# Tingle_v3.net
KiCad netlist of a schematic drawn in EAGLE
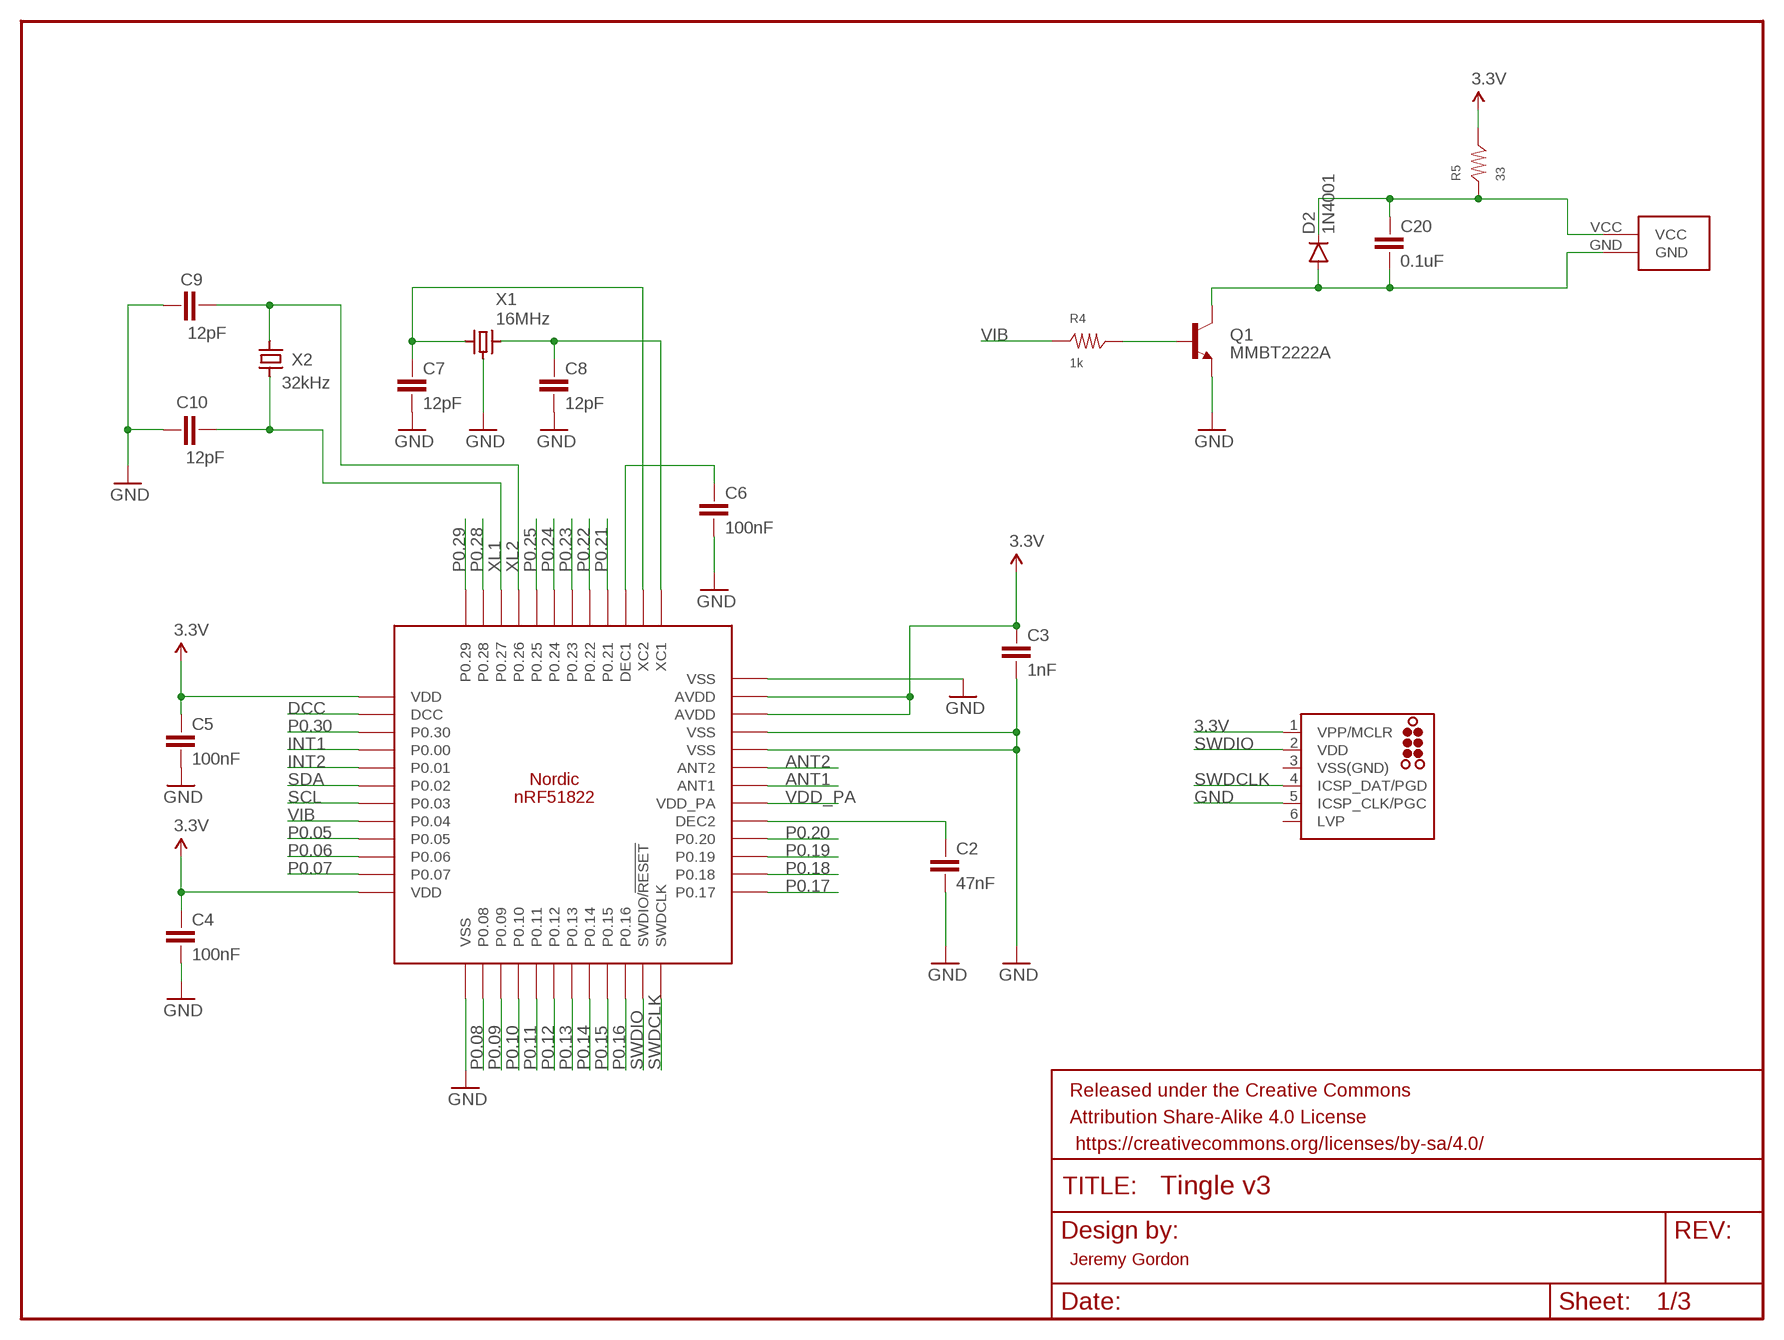
[diagram p0: schematic, sheet 1]
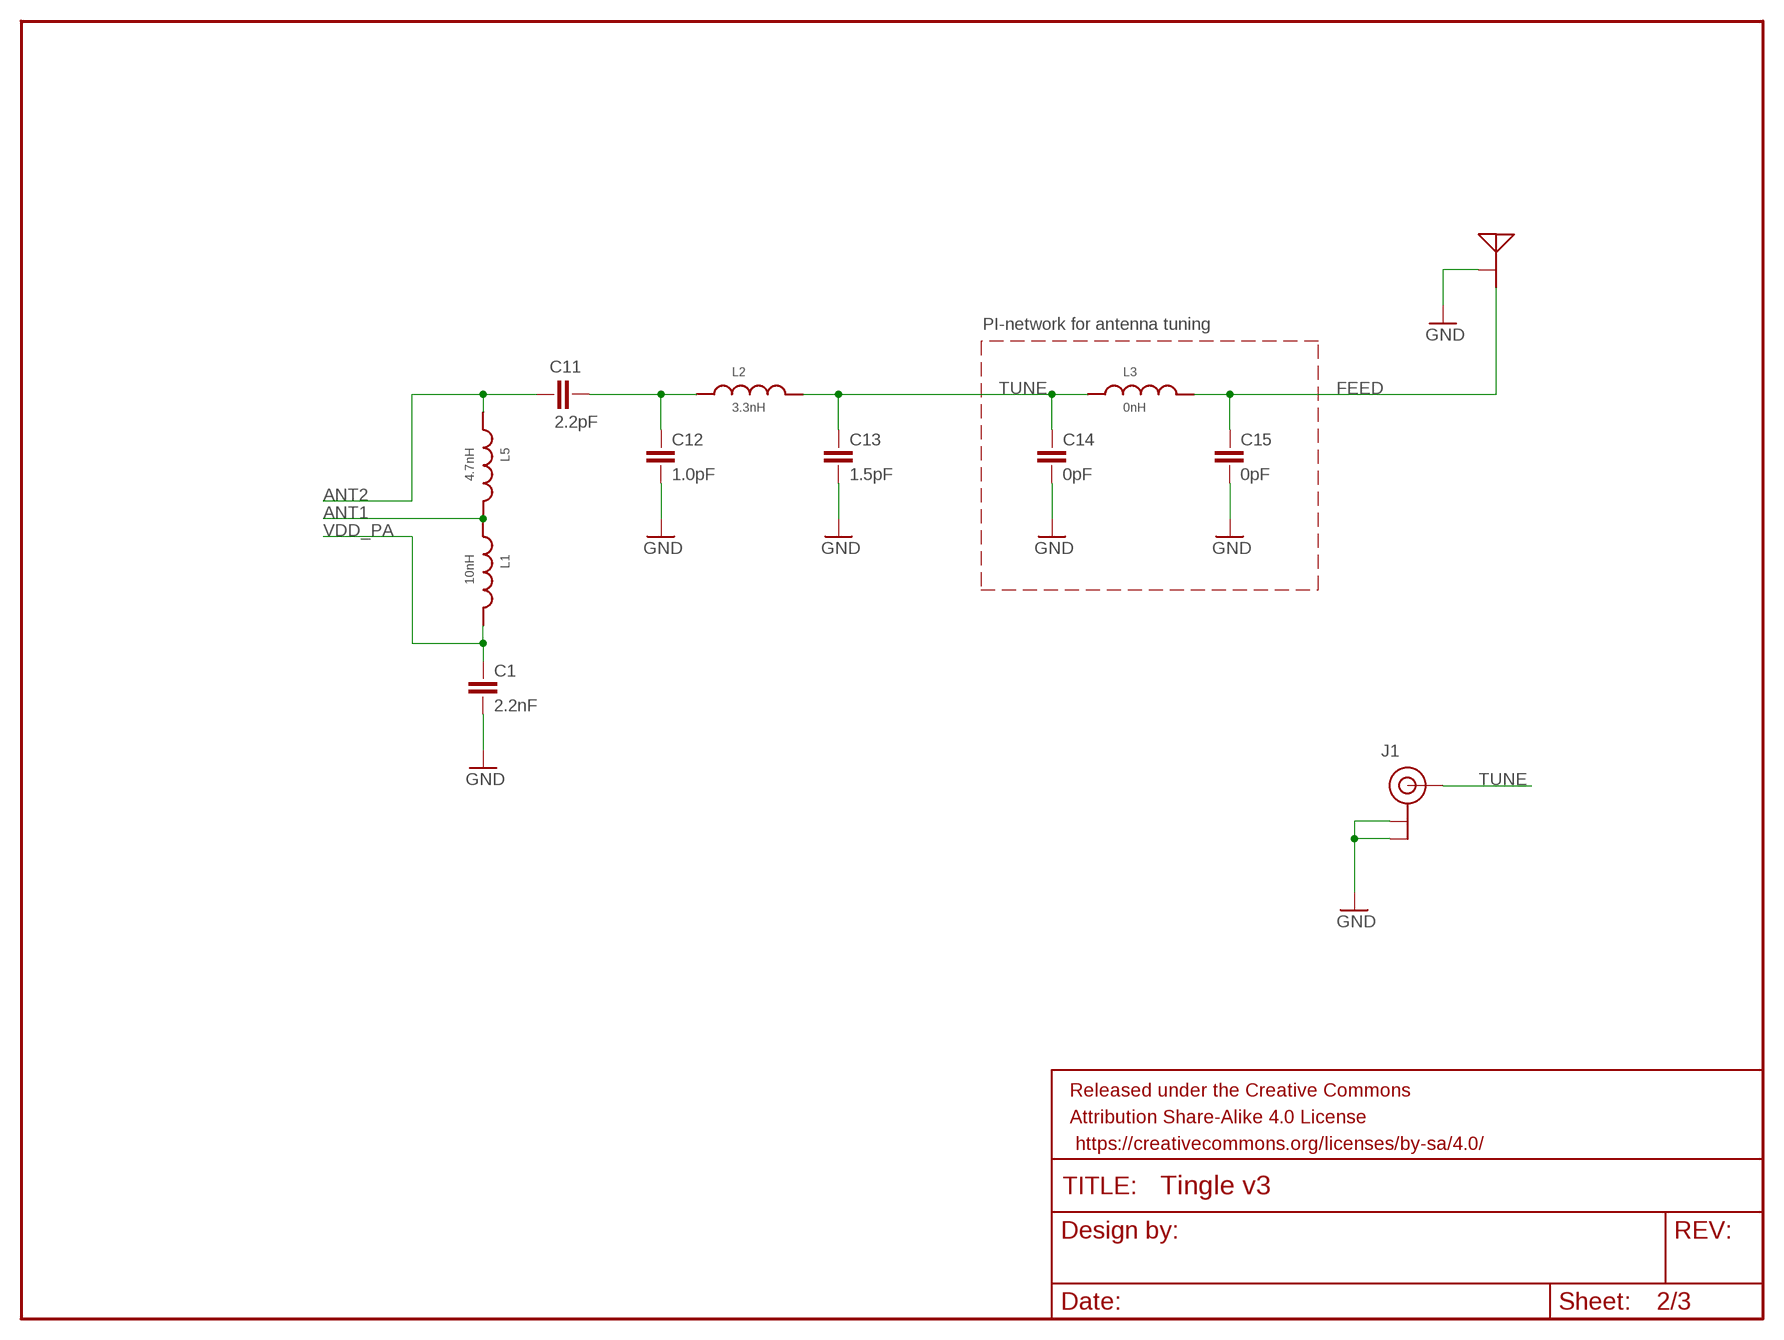
[diagram p1: schematic, sheet 2]
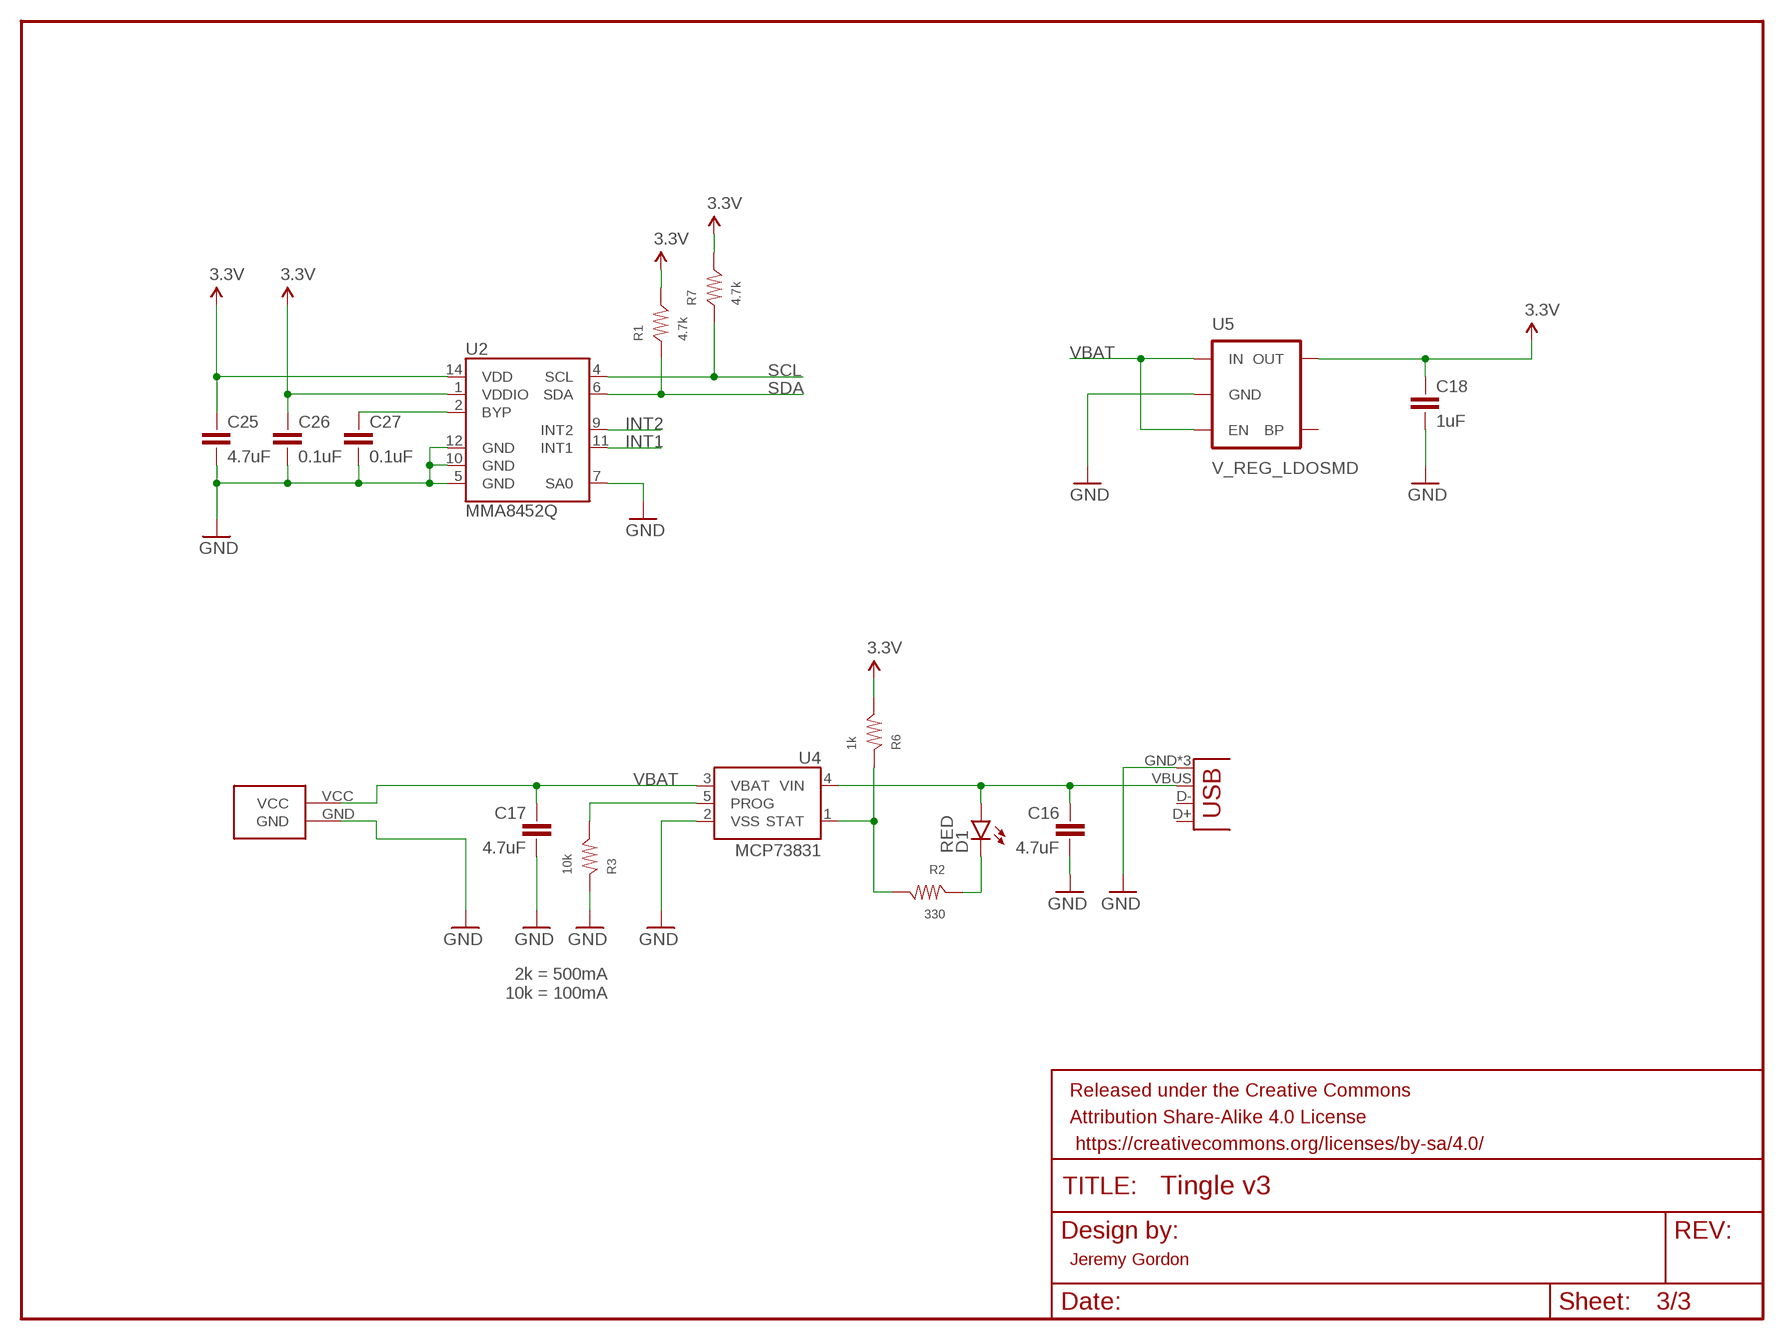
[diagram p2: schematic, sheet 3]

(export (version "E")
  (design (tool "Eeschema 10.0.6"))
  (components
    (comp (ref "C16")
      (value "4.7uF")
      (footprint "eagle-import:CAP-402")
      (libsource (lib "eagle-import") (part "CAP-402"))
    )
    (comp (ref "C17")
      (value "4.7uF")
      (footprint "eagle-import:CAP-402")
      (libsource (lib "eagle-import") (part "CAP-402"))
    )
    (comp (ref "C18")
      (value "1uF")
      (footprint "eagle-import:CAP-402")
      (libsource (lib "eagle-import") (part "CAP-402"))
    )
    (comp (ref "C25")
      (value "4.7uF")
      (footprint "eagle-import:CAP-402")
      (libsource (lib "eagle-import") (part "CAP-402"))
    )
    (comp (ref "C26")
      (value "0.1uF")
      (footprint "eagle-import:CAP-402")
      (libsource (lib "eagle-import") (part "CAP-402"))
    )
    (comp (ref "C27")
      (value "0.1uF")
      (footprint "eagle-import:CAP-402")
      (libsource (lib "eagle-import") (part "CAP-402"))
    )
    (comp (ref "D1")
      (value "RED")
      (footprint "eagle-import:LED-0603")
      (libsource (lib "eagle-import") (part "LED-RED0603"))
    )
    (comp (ref "FRAME2")
      (value "FRAME-LETTER")
      (footprint "eagle-import:CREATIVE_COMMONS")
      (libsource (lib "eagle-import") (part "FRAME-LETTER"))
    )
    (comp (ref "JP2")
      (value "USB-MICROB")
      (footprint "eagle-import:USB-MICROB")
      (libsource (lib "eagle-import") (part "USB-MICROB"))
    )
    (comp (ref "R1")
      (value "4.7k")
      (footprint "eagle-import:RES-402")
      (libsource (lib "eagle-import") (part "RES-402"))
    )
    (comp (ref "R2")
      (value "330")
      (footprint "eagle-import:RES-402")
      (libsource (lib "eagle-import") (part "RES-402"))
    )
    (comp (ref "R3")
      (value "10k")
      (footprint "eagle-import:RES-402")
      (libsource (lib "eagle-import") (part "RES-402"))
    )
    (comp (ref "R6")
      (value "1k")
      (footprint "eagle-import:RES-402")
      (libsource (lib "eagle-import") (part "RES-402"))
    )
    (comp (ref "R7")
      (value "4.7k")
      (footprint "eagle-import:RES-402")
      (libsource (lib "eagle-import") (part "RES-402"))
    )
    (comp (ref "U$3")
      (value "CONN")
      (footprint "eagle-import:CONN")
      (libsource (lib "eagle-import") (part "CONN"))
    )
    (comp (ref "U2")
      (value "MMA8452Q")
      (footprint "eagle-import:QFN-16_0.5MM")
      (libsource (lib "eagle-import") (part "MMA8452Q"))
    )
    (comp (ref "U4")
      (value "MCP73831")
      (footprint "eagle-import:SOT23-5")
      (libsource (lib "eagle-import") (part "MCP73831"))
    )
    (comp (ref "U5")
      (value "V_REG_LDOSMD")
      (footprint "eagle-import:SOT23-5")
      (libsource (lib "eagle-import") (part "V_REG_LDOSMD"))
    )
    (comp (ref "C2")
      (value "47nF")
      (footprint "eagle-import:CAP-402")
      (libsource (lib "eagle-import") (part "CAP-402"))
    )
    (comp (ref "C3")
      (value "1nF")
      (footprint "eagle-import:CAP-402")
      (libsource (lib "eagle-import") (part "CAP-402"))
    )
    (comp (ref "C4")
      (value "100nF")
      (footprint "eagle-import:CAP-402")
      (libsource (lib "eagle-import") (part "CAP-402"))
    )
    (comp (ref "C5")
      (value "100nF")
      (footprint "eagle-import:CAP-402")
      (libsource (lib "eagle-import") (part "CAP-402"))
    )
    (comp (ref "C6")
      (value "100nF")
      (footprint "eagle-import:CAP-402")
      (libsource (lib "eagle-import") (part "CAP-402"))
    )
    (comp (ref "C7")
      (value "12pF")
      (footprint "eagle-import:CAP-402")
      (libsource (lib "eagle-import") (part "CAP-402"))
    )
    (comp (ref "C8")
      (value "12pF")
      (footprint "eagle-import:CAP-402")
      (libsource (lib "eagle-import") (part "CAP-402"))
    )
    (comp (ref "C9")
      (value "12pF")
      (footprint "eagle-import:CAP-402")
      (libsource (lib "eagle-import") (part "CAP-402"))
    )
    (comp (ref "C10")
      (value "12pF")
      (footprint "eagle-import:CAP-402")
      (libsource (lib "eagle-import") (part "CAP-402"))
    )
    (comp (ref "C20")
      (value "0.1uF")
      (footprint "eagle-import:CAP-402")
      (libsource (lib "eagle-import") (part "CAP-402"))
    )
    (comp (ref "D2")
      (value "1N4001")
      (footprint "eagle-import:SOD-323")
      (libsource (lib "eagle-import") (part "DIODESOD"))
    )
    (comp (ref "FRAME1")
      (value "FRAME-LETTER")
      (footprint "eagle-import:CREATIVE_COMMONS")
      (libsource (lib "eagle-import") (part "FRAME-LETTER"))
    )
    (comp (ref "J2")
      (value "TC2030-MCP-NL")
      (footprint "eagle-import:TC2030-MCP-NL")
      (libsource (lib "eagle-import") (part "TC2030-MCP-NL"))
    )
    (comp (ref "Q1")
      (value "MMBT2222A")
      (footprint "eagle-import:SOT23-3")
      (libsource (lib "eagle-import") (part "TRANSISTOR_NPNMMBT2222A"))
    )
    (comp (ref "R4")
      (value "1k")
      (footprint "eagle-import:RES-402")
      (libsource (lib "eagle-import") (part "RES-402"))
    )
    (comp (ref "R5")
      (value "33")
      (footprint "eagle-import:RES-402")
      (libsource (lib "eagle-import") (part "RES-402"))
    )
    (comp (ref "U$1")
      (value "CONN")
      (footprint "eagle-import:CONN")
      (libsource (lib "eagle-import") (part "CONN"))
    )
    (comp (ref "U1")
      (value "NRF51822")
      (footprint "eagle-import:NRF51822")
      (libsource (lib "eagle-import") (part "NRF51822"))
    )
    (comp (ref "X1")
      (value "16MHz")
      (footprint "eagle-import:CRYSTAL-2520")
      (libsource (lib "eagle-import") (part "CRYSTAL-GND2520"))
    )
    (comp (ref "X2")
      (value "32kHz")
      (footprint "eagle-import:CRYSTAL-3215")
      (libsource (lib "eagle-import") (part "CRYSTAL3215"))
    )
    (comp (ref "C1")
      (value "2.2nF")
      (footprint "eagle-import:CAP-402")
      (libsource (lib "eagle-import") (part "CAP-402"))
    )
    (comp (ref "C11")
      (value "2.2pF")
      (footprint "eagle-import:CAP-402")
      (libsource (lib "eagle-import") (part "CAP-402"))
    )
    (comp (ref "C12")
      (value "1.0pF")
      (footprint "eagle-import:CAP-402")
      (libsource (lib "eagle-import") (part "CAP-402"))
    )
    (comp (ref "C13")
      (value "1.5pF")
      (footprint "eagle-import:CAP-402")
      (libsource (lib "eagle-import") (part "CAP-402"))
    )
    (comp (ref "C14")
      (value "0pF")
      (footprint "eagle-import:CAP-402")
      (libsource (lib "eagle-import") (part "CAP-402"))
    )
    (comp (ref "C15")
      (value "0pF")
      (footprint "eagle-import:CAP-402")
      (libsource (lib "eagle-import") (part "CAP-402"))
    )
    (comp (ref "FRAME3")
      (value "FRAME-LETTER")
      (footprint "eagle-import:CREATIVE_COMMONS")
      (libsource (lib "eagle-import") (part "FRAME-LETTER"))
    )
    (comp (ref "J1")
      (value "U.FL")
      (footprint "eagle-import:U.FL")
      (libsource (lib "eagle-import") (part "U.FL"))
    )
    (comp (ref "L1")
      (value "10nH")
      (footprint "eagle-import:IND-402")
      (libsource (lib "eagle-import") (part "IND-402"))
    )
    (comp (ref "L2")
      (value "3.3nH")
      (footprint "eagle-import:IND-402")
      (libsource (lib "eagle-import") (part "IND-402"))
    )
    (comp (ref "L3")
      (value "0nH")
      (footprint "eagle-import:IND-402")
      (libsource (lib "eagle-import") (part "IND-402"))
    )
    (comp (ref "L5")
      (value "4.7nH")
      (footprint "eagle-import:IND-402")
      (libsource (lib "eagle-import") (part "IND-402"))
    )
    (comp (ref "U$2")
      (value "MEANDER-ANT")
      (footprint "eagle-import:MEANDER-ANT")
      (libsource (lib "eagle-import") (part "MEANDER-ANT"))
    )
  )
  (nets
    (net (code "1") (name "3.3V") (class "Default")
      (node (ref "C18") (pin "2") (pinfunction "1_2") (pintype "bidirectional"))
      (node (ref "C25") (pin "2") (pinfunction "1_2") (pintype "bidirectional"))
      (node (ref "C26") (pin "2") (pinfunction "1_2") (pintype "bidirectional"))
      (node (ref "C3") (pin "2") (pinfunction "1_2") (pintype "bidirectional"))
      (node (ref "C4") (pin "2") (pinfunction "1_2") (pintype "bidirectional"))
      (node (ref "C5") (pin "2") (pinfunction "1_2") (pintype "bidirectional"))
      (node (ref "J2") (pin "1") (pinfunction "VPP/MCLR_1") (pintype "passive"))
      (node (ref "R1") (pin "2") (pinfunction "P$2_2") (pintype "bidirectional"))
      (node (ref "R5") (pin "2") (pinfunction "P$2_2") (pintype "bidirectional"))
      (node (ref "R6") (pin "2") (pinfunction "P$2_2") (pintype "bidirectional"))
      (node (ref "R7") (pin "2") (pinfunction "P$2_2") (pintype "bidirectional"))
      (node (ref "U1") (pin "AVDD@1") (pinfunction "AVDD_AVDD@1") (pintype "bidirectional"))
      (node (ref "U1") (pin "AVDD@2") (pinfunction "AVDD_AVDD@2") (pintype "bidirectional"))
      (node (ref "U1") (pin "VDD@1") (pinfunction "VDD_VDD@1") (pintype "bidirectional"))
      (node (ref "U1") (pin "VDD@2") (pinfunction "VDD_VDD@2") (pintype "bidirectional"))
      (node (ref "U2") (pin "1") (pinfunction "VDDIO_1") (pintype "bidirectional"))
      (node (ref "U2") (pin "14") (pinfunction "VDD_14") (pintype "bidirectional"))
      (node (ref "U5") (pin "5") (pinfunction "OUT_5") (pintype "passive"))
    )
    (net (code "2") (name "ANT1") (class "Default")
      (node (ref "L1") (pin "1") (pinfunction "P$1_1") (pintype "bidirectional"))
      (node (ref "L5") (pin "2") (pinfunction "P$2_2") (pintype "bidirectional"))
      (node (ref "U1") (pin "ANT1") (pinfunction "ANT1_ANT1") (pintype "bidirectional"))
    )
    (net (code "3") (name "ANT2") (class "Default")
      (node (ref "C11") (pin "2") (pinfunction "1_2") (pintype "bidirectional"))
      (node (ref "L5") (pin "1") (pinfunction "P$1_1") (pintype "bidirectional"))
      (node (ref "U1") (pin "ANT2") (pinfunction "ANT2_ANT2") (pintype "bidirectional"))
    )
    (net (code "4") (name "DCC") (class "Default")
      (node (ref "U1") (pin "DCC") (pinfunction "DCC_DCC") (pintype "bidirectional"))
    )
    (net (code "5") (name "FEED") (class "Default")
      (node (ref "C15") (pin "2") (pinfunction "1_2") (pintype "bidirectional"))
      (node (ref "L3") (pin "2") (pinfunction "P$2_2") (pintype "bidirectional"))
      (node (ref "U$2") (pin "FEED") (pinfunction "FEED_FEED") (pintype "bidirectional"))
    )
    (net (code "6") (name "GND") (class "Default")
      (node (ref "C1") (pin "1") (pinfunction "2_1") (pintype "bidirectional"))
      (node (ref "C10") (pin "2") (pinfunction "1_2") (pintype "bidirectional"))
      (node (ref "C12") (pin "1") (pinfunction "2_1") (pintype "bidirectional"))
      (node (ref "C13") (pin "1") (pinfunction "2_1") (pintype "bidirectional"))
      (node (ref "C14") (pin "1") (pinfunction "2_1") (pintype "bidirectional"))
      (node (ref "C15") (pin "1") (pinfunction "2_1") (pintype "bidirectional"))
      (node (ref "C16") (pin "1") (pinfunction "2_1") (pintype "bidirectional"))
      (node (ref "C17") (pin "1") (pinfunction "2_1") (pintype "bidirectional"))
      (node (ref "C18") (pin "1") (pinfunction "2_1") (pintype "bidirectional"))
      (node (ref "C2") (pin "1") (pinfunction "2_1") (pintype "bidirectional"))
      (node (ref "C25") (pin "1") (pinfunction "2_1") (pintype "bidirectional"))
      (node (ref "C26") (pin "1") (pinfunction "2_1") (pintype "bidirectional"))
      (node (ref "C27") (pin "1") (pinfunction "2_1") (pintype "bidirectional"))
      (node (ref "C3") (pin "1") (pinfunction "2_1") (pintype "bidirectional"))
      (node (ref "C4") (pin "1") (pinfunction "2_1") (pintype "bidirectional"))
      (node (ref "C5") (pin "1") (pinfunction "2_1") (pintype "bidirectional"))
      (node (ref "C6") (pin "1") (pinfunction "2_1") (pintype "bidirectional"))
      (node (ref "C7") (pin "1") (pinfunction "2_1") (pintype "bidirectional"))
      (node (ref "C8") (pin "1") (pinfunction "2_1") (pintype "bidirectional"))
      (node (ref "C9") (pin "2") (pinfunction "1_2") (pintype "bidirectional"))
      (node (ref "J1") (pin "P$1") (pinfunction "GND_P$1") (pintype "bidirectional"))
      (node (ref "J1") (pin "P$2") (pinfunction "GND_P$2") (pintype "bidirectional"))
      (node (ref "J2") (pin "5") (pinfunction "ICSP_CLK/PGC_5") (pintype "output"))
      (node (ref "JP2") (pin "GND") (pinfunction "GND_GND") (pintype "bidirectional"))
      (node (ref "JP2") (pin "MT1") (pinfunction "GND_MT1") (pintype "bidirectional"))
      (node (ref "JP2") (pin "MT2") (pinfunction "GND_MT2") (pintype "bidirectional"))
      (node (ref "Q1") (pin "2") (pinfunction "E_2") (pintype "passive"))
      (node (ref "R3") (pin "1") (pinfunction "P$1_1") (pintype "bidirectional"))
      (node (ref "U$2") (pin "GND") (pinfunction "GND_GND") (pintype "bidirectional"))
      (node (ref "U$3") (pin "GND") (pinfunction "GND_GND") (pintype "bidirectional"))
      (node (ref "U1") (pin "VSS@1") (pinfunction "VSS_VSS@1") (pintype "bidirectional"))
      (node (ref "U1") (pin "VSS@2") (pinfunction "VSS_VSS@2") (pintype "bidirectional"))
      (node (ref "U1") (pin "VSS@3") (pinfunction "VSS_VSS@3") (pintype "bidirectional"))
      (node (ref "U1") (pin "VSS@4") (pinfunction "VSS_VSS@4") (pintype "bidirectional"))
      (node (ref "U2") (pin "10") (pinfunction "GND_10") (pintype "bidirectional"))
      (node (ref "U2") (pin "12") (pinfunction "GND_12") (pintype "bidirectional"))
      (node (ref "U2") (pin "5") (pinfunction "GND_5") (pintype "bidirectional"))
      (node (ref "U2") (pin "7") (pinfunction "SA0_7") (pintype "bidirectional"))
      (node (ref "U4") (pin "2") (pinfunction "VSS_2") (pintype "power_in"))
      (node (ref "U5") (pin "2") (pinfunction "GND_2") (pintype "input"))
      (node (ref "X1") (pin "GND@1") (pinfunction "GND_GND@1") (pintype "bidirectional"))
      (node (ref "X1") (pin "GND@2") (pinfunction "GND_GND@2") (pintype "bidirectional"))
    )
    (net (code "7") (name "INT1") (class "Default")
      (node (ref "U1") (pin "P0.00") (pinfunction "P0.00_P0.00") (pintype "bidirectional"))
      (node (ref "U2") (pin "11") (pinfunction "INT1_11") (pintype "bidirectional"))
    )
    (net (code "8") (name "INT2") (class "Default")
      (node (ref "U1") (pin "P0.01") (pinfunction "P0.01_P0.01") (pintype "bidirectional"))
      (node (ref "U2") (pin "9") (pinfunction "INT2_9") (pintype "bidirectional"))
    )
    (net (code "9") (name "Net-(C2-1)") (class "Default")
      (node (ref "C2") (pin "2") (pinfunction "1_2") (pintype "bidirectional"))
      (node (ref "U1") (pin "DEC2") (pinfunction "DEC2_DEC2") (pintype "bidirectional"))
    )
    (net (code "10") (name "Net-(C6-1)") (class "Default")
      (node (ref "C6") (pin "2") (pinfunction "1_2") (pintype "bidirectional"))
      (node (ref "U1") (pin "DEC1") (pinfunction "DEC1_DEC1") (pintype "bidirectional"))
    )
    (net (code "11") (name "Net-(C7-1)") (class "Default")
      (node (ref "C7") (pin "2") (pinfunction "1_2") (pintype "bidirectional"))
      (node (ref "U1") (pin "XC2") (pinfunction "XC2_XC2") (pintype "bidirectional"))
      (node (ref "X1") (pin "1") (pinfunction "1_1") (pintype "bidirectional"))
    )
    (net (code "12") (name "Net-(C8-1)") (class "Default")
      (node (ref "C8") (pin "2") (pinfunction "1_2") (pintype "bidirectional"))
      (node (ref "U1") (pin "XC1") (pinfunction "XC1_XC1") (pintype "bidirectional"))
      (node (ref "X1") (pin "3") (pinfunction "3_3") (pintype "bidirectional"))
    )
    (net (code "13") (name "Net-(C11-2)") (class "Default")
      (node (ref "C11") (pin "1") (pinfunction "2_1") (pintype "bidirectional"))
      (node (ref "C12") (pin "2") (pinfunction "1_2") (pintype "bidirectional"))
      (node (ref "L2") (pin "1") (pinfunction "P$1_1") (pintype "bidirectional"))
    )
    (net (code "14") (name "Net-(C16-1)") (class "Default")
      (node (ref "C16") (pin "2") (pinfunction "1_2") (pintype "bidirectional"))
      (node (ref "D1") (pin "A") (pinfunction "A_A") (pintype "passive"))
      (node (ref "JP2") (pin "VBUS") (pinfunction "VBUS_VBUS") (pintype "bidirectional"))
      (node (ref "U4") (pin "4") (pinfunction "VIN_4") (pintype "power_in"))
    )
    (net (code "15") (name "Net-(C20-1)") (class "Default")
      (node (ref "C20") (pin "2") (pinfunction "1_2") (pintype "bidirectional"))
      (node (ref "D2") (pin "C") (pinfunction "C_C") (pintype "passive"))
      (node (ref "R5") (pin "1") (pinfunction "P$1_1") (pintype "bidirectional"))
      (node (ref "U$1") (pin "VCC") (pinfunction "VCC_VCC") (pintype "bidirectional"))
    )
    (net (code "16") (name "Net-(C20-2)") (class "Default")
      (node (ref "C20") (pin "1") (pinfunction "2_1") (pintype "bidirectional"))
      (node (ref "D2") (pin "A") (pinfunction "A_A") (pintype "passive"))
      (node (ref "Q1") (pin "3") (pinfunction "C_3") (pintype "passive"))
      (node (ref "U$1") (pin "GND") (pinfunction "GND_GND") (pintype "bidirectional"))
    )
    (net (code "17") (name "Net-(C27-1)") (class "Default")
      (node (ref "C27") (pin "2") (pinfunction "1_2") (pintype "bidirectional"))
      (node (ref "U2") (pin "2") (pinfunction "BYP_2") (pintype "bidirectional"))
    )
    (net (code "18") (name "Net-(Q1-B)") (class "Default")
      (node (ref "Q1") (pin "1") (pinfunction "B_1") (pintype "passive"))
      (node (ref "R4") (pin "2") (pinfunction "P$2_2") (pintype "bidirectional"))
    )
    (net (code "19") (name "Net-(R2-P$1)") (class "Default")
      (node (ref "D1") (pin "C") (pinfunction "C_C") (pintype "passive"))
      (node (ref "R2") (pin "1") (pinfunction "P$1_1") (pintype "bidirectional"))
    )
    (net (code "20") (name "Net-(R2-P$2)") (class "Default")
      (node (ref "R2") (pin "2") (pinfunction "P$2_2") (pintype "bidirectional"))
      (node (ref "R6") (pin "1") (pinfunction "P$1_1") (pintype "bidirectional"))
      (node (ref "U4") (pin "1") (pinfunction "STAT_1") (pintype "output"))
    )
    (net (code "21") (name "Net-(R3-P$2)") (class "Default")
      (node (ref "R3") (pin "2") (pinfunction "P$2_2") (pintype "bidirectional"))
      (node (ref "U4") (pin "5") (pinfunction "PROG_5") (pintype "input"))
    )
    (net (code "22") (name "P0.05") (class "Default")
      (node (ref "U1") (pin "P0.05") (pinfunction "P0.05_P0.05") (pintype "bidirectional"))
    )
    (net (code "23") (name "P0.06") (class "Default")
      (node (ref "U1") (pin "P0.06") (pinfunction "P0.06_P0.06") (pintype "bidirectional"))
    )
    (net (code "24") (name "P0.07") (class "Default")
      (node (ref "U1") (pin "P0.07") (pinfunction "P0.07_P0.07") (pintype "bidirectional"))
    )
    (net (code "25") (name "P0.08") (class "Default")
      (node (ref "U1") (pin "P0.08") (pinfunction "P0.08_P0.08") (pintype "bidirectional"))
    )
    (net (code "26") (name "P0.09") (class "Default")
      (node (ref "U1") (pin "P0.09") (pinfunction "P0.09_P0.09") (pintype "bidirectional"))
    )
    (net (code "27") (name "P0.10") (class "Default")
      (node (ref "U1") (pin "P0.10") (pinfunction "P0.10_P0.10") (pintype "bidirectional"))
    )
    (net (code "28") (name "P0.11") (class "Default")
      (node (ref "U1") (pin "P0.11") (pinfunction "P0.11_P0.11") (pintype "bidirectional"))
    )
    (net (code "29") (name "P0.12") (class "Default")
      (node (ref "U1") (pin "P0.12") (pinfunction "P0.12_P0.12") (pintype "bidirectional"))
    )
    (net (code "30") (name "P0.13") (class "Default")
      (node (ref "U1") (pin "P0.13") (pinfunction "P0.13_P0.13") (pintype "bidirectional"))
    )
    (net (code "31") (name "P0.14") (class "Default")
      (node (ref "U1") (pin "P0.14") (pinfunction "P0.14_P0.14") (pintype "bidirectional"))
    )
    (net (code "32") (name "P0.15") (class "Default")
      (node (ref "U1") (pin "P0.15") (pinfunction "P0.15_P0.15") (pintype "bidirectional"))
    )
    (net (code "33") (name "P0.16") (class "Default")
      (node (ref "U1") (pin "P0.16") (pinfunction "P0.16_P0.16") (pintype "bidirectional"))
    )
    (net (code "34") (name "P0.17") (class "Default")
      (node (ref "U1") (pin "P0.17") (pinfunction "P0.17_P0.17") (pintype "bidirectional"))
    )
    (net (code "35") (name "P0.18") (class "Default")
      (node (ref "U1") (pin "P0.18") (pinfunction "P0.18_P0.18") (pintype "bidirectional"))
    )
    (net (code "36") (name "P0.19") (class "Default")
      (node (ref "U1") (pin "P0.19") (pinfunction "P0.19_P0.19") (pintype "bidirectional"))
    )
    (net (code "37") (name "P0.20") (class "Default")
      (node (ref "U1") (pin "P0.20") (pinfunction "P0.20_P0.20") (pintype "bidirectional"))
    )
    (net (code "38") (name "P0.21") (class "Default")
      (node (ref "U1") (pin "P0.21") (pinfunction "P0.21_P0.21") (pintype "bidirectional"))
    )
    (net (code "39") (name "P0.22") (class "Default")
      (node (ref "U1") (pin "P0.22") (pinfunction "P0.22_P0.22") (pintype "bidirectional"))
    )
    (net (code "40") (name "P0.23") (class "Default")
      (node (ref "U1") (pin "P0.23") (pinfunction "P0.23_P0.23") (pintype "bidirectional"))
    )
    (net (code "41") (name "P0.24") (class "Default")
      (node (ref "U1") (pin "P0.24") (pinfunction "P0.24_P0.24") (pintype "bidirectional"))
    )
    (net (code "42") (name "P0.25") (class "Default")
      (node (ref "U1") (pin "P0.25") (pinfunction "P0.25_P0.25") (pintype "bidirectional"))
    )
    (net (code "43") (name "P0.28") (class "Default")
      (node (ref "U1") (pin "P0.28") (pinfunction "P0.28_P0.28") (pintype "bidirectional"))
    )
    (net (code "44") (name "P0.29") (class "Default")
      (node (ref "U1") (pin "P0.29") (pinfunction "P0.29_P0.29") (pintype "bidirectional"))
    )
    (net (code "45") (name "P0.30") (class "Default")
      (node (ref "U1") (pin "P0.30") (pinfunction "P0.30_P0.30") (pintype "bidirectional"))
    )
    (net (code "46") (name "SCL") (class "Default")
      (node (ref "R7") (pin "1") (pinfunction "P$1_1") (pintype "bidirectional"))
      (node (ref "U1") (pin "P0.03") (pinfunction "P0.03_P0.03") (pintype "bidirectional"))
      (node (ref "U2") (pin "4") (pinfunction "SCL_4") (pintype "bidirectional"))
    )
    (net (code "47") (name "SDA") (class "Default")
      (node (ref "R1") (pin "1") (pinfunction "P$1_1") (pintype "bidirectional"))
      (node (ref "U1") (pin "P0.02") (pinfunction "P0.02_P0.02") (pintype "bidirectional"))
      (node (ref "U2") (pin "6") (pinfunction "SDA_6") (pintype "bidirectional"))
    )
    (net (code "48") (name "SWDCLK") (class "Default")
      (node (ref "J2") (pin "4") (pinfunction "ICSP_DAT/PGD_4") (pintype "bidirectional"))
      (node (ref "U1") (pin "SWDCLK") (pinfunction "SWDCLK_SWDCLK") (pintype "bidirectional"))
    )
    (net (code "49") (name "SWDIO") (class "Default")
      (node (ref "J2") (pin "2") (pinfunction "VDD_2") (pintype "power_in"))
      (node (ref "U1") (pin "SWDIO/!RESET") (pinfunction "SWDIO/~{RESET}_SWDIO/!RESET") (pintype "bidirectional"))
    )
    (net (code "50") (name "TUNE") (class "Default")
      (node (ref "C13") (pin "2") (pinfunction "1_2") (pintype "bidirectional"))
      (node (ref "C14") (pin "2") (pinfunction "1_2") (pintype "bidirectional"))
      (node (ref "J1") (pin "P$3") (pinfunction "SIGNAL_P$3") (pintype "bidirectional"))
      (node (ref "L2") (pin "2") (pinfunction "P$2_2") (pintype "bidirectional"))
      (node (ref "L3") (pin "1") (pinfunction "P$1_1") (pintype "bidirectional"))
    )
    (net (code "51") (name "VBAT") (class "Default")
      (node (ref "C17") (pin "2") (pinfunction "1_2") (pintype "bidirectional"))
      (node (ref "U$3") (pin "VCC") (pinfunction "VCC_VCC") (pintype "bidirectional"))
      (node (ref "U4") (pin "3") (pinfunction "VBAT_3") (pintype "power_in"))
      (node (ref "U5") (pin "1") (pinfunction "IN_1") (pintype "input"))
      (node (ref "U5") (pin "3") (pinfunction "EN_3") (pintype "input"))
    )
    (net (code "52") (name "VDD_PA") (class "Default")
      (node (ref "C1") (pin "2") (pinfunction "1_2") (pintype "bidirectional"))
      (node (ref "L1") (pin "2") (pinfunction "P$2_2") (pintype "bidirectional"))
      (node (ref "U1") (pin "VDD_PA") (pinfunction "VDD_PA_VDD_PA") (pintype "bidirectional"))
    )
    (net (code "53") (name "VIB") (class "Default")
      (node (ref "R4") (pin "1") (pinfunction "P$1_1") (pintype "bidirectional"))
      (node (ref "U1") (pin "P0.04") (pinfunction "P0.04_P0.04") (pintype "bidirectional"))
    )
    (net (code "54") (name "VSS(GND)") (class "Default")
      (node (ref "J2") (pin "3") (pinfunction "VSS(GND)_3") (pintype "power_in"))
    )
    (net (code "55") (name "XL1") (class "Default")
      (node (ref "C10") (pin "1") (pinfunction "2_1") (pintype "bidirectional"))
      (node (ref "U1") (pin "P0.27") (pinfunction "P0.27_P0.27") (pintype "bidirectional"))
      (node (ref "X2") (pin "P$1") (pinfunction "1_P$1") (pintype "bidirectional"))
    )
    (net (code "56") (name "XL2") (class "Default")
      (node (ref "C9") (pin "1") (pinfunction "2_1") (pintype "bidirectional"))
      (node (ref "U1") (pin "P0.26") (pinfunction "P0.26_P0.26") (pintype "bidirectional"))
      (node (ref "X2") (pin "P$2") (pinfunction "3_P$2") (pintype "bidirectional"))
    )
    (net (code "57") (name "unconnected-(J2-LVP-Pad6)") (class "Default")
      (node (ref "J2") (pin "6") (pinfunction "LVP_6") (pintype "bidirectional"))
    )
    (net (code "58") (name "unconnected-(JP2-PadD+)") (class "Default")
      (node (ref "JP2") (pin "D+") (pinfunction "D+_D+") (pintype "bidirectional"))
    )
    (net (code "59") (name "unconnected-(JP2-PadD-)") (class "Default")
      (node (ref "JP2") (pin "D-") (pinfunction "D-_D-") (pintype "bidirectional"))
    )
    (net (code "60") (name "unconnected-(U5-BP-Pad4)") (class "Default")
      (node (ref "U5") (pin "4") (pinfunction "BP_4") (pintype "input"))
    )
  )
)
